# I2C_decagon_straight.net
KiCad netlist of a schematic drawn in EAGLE
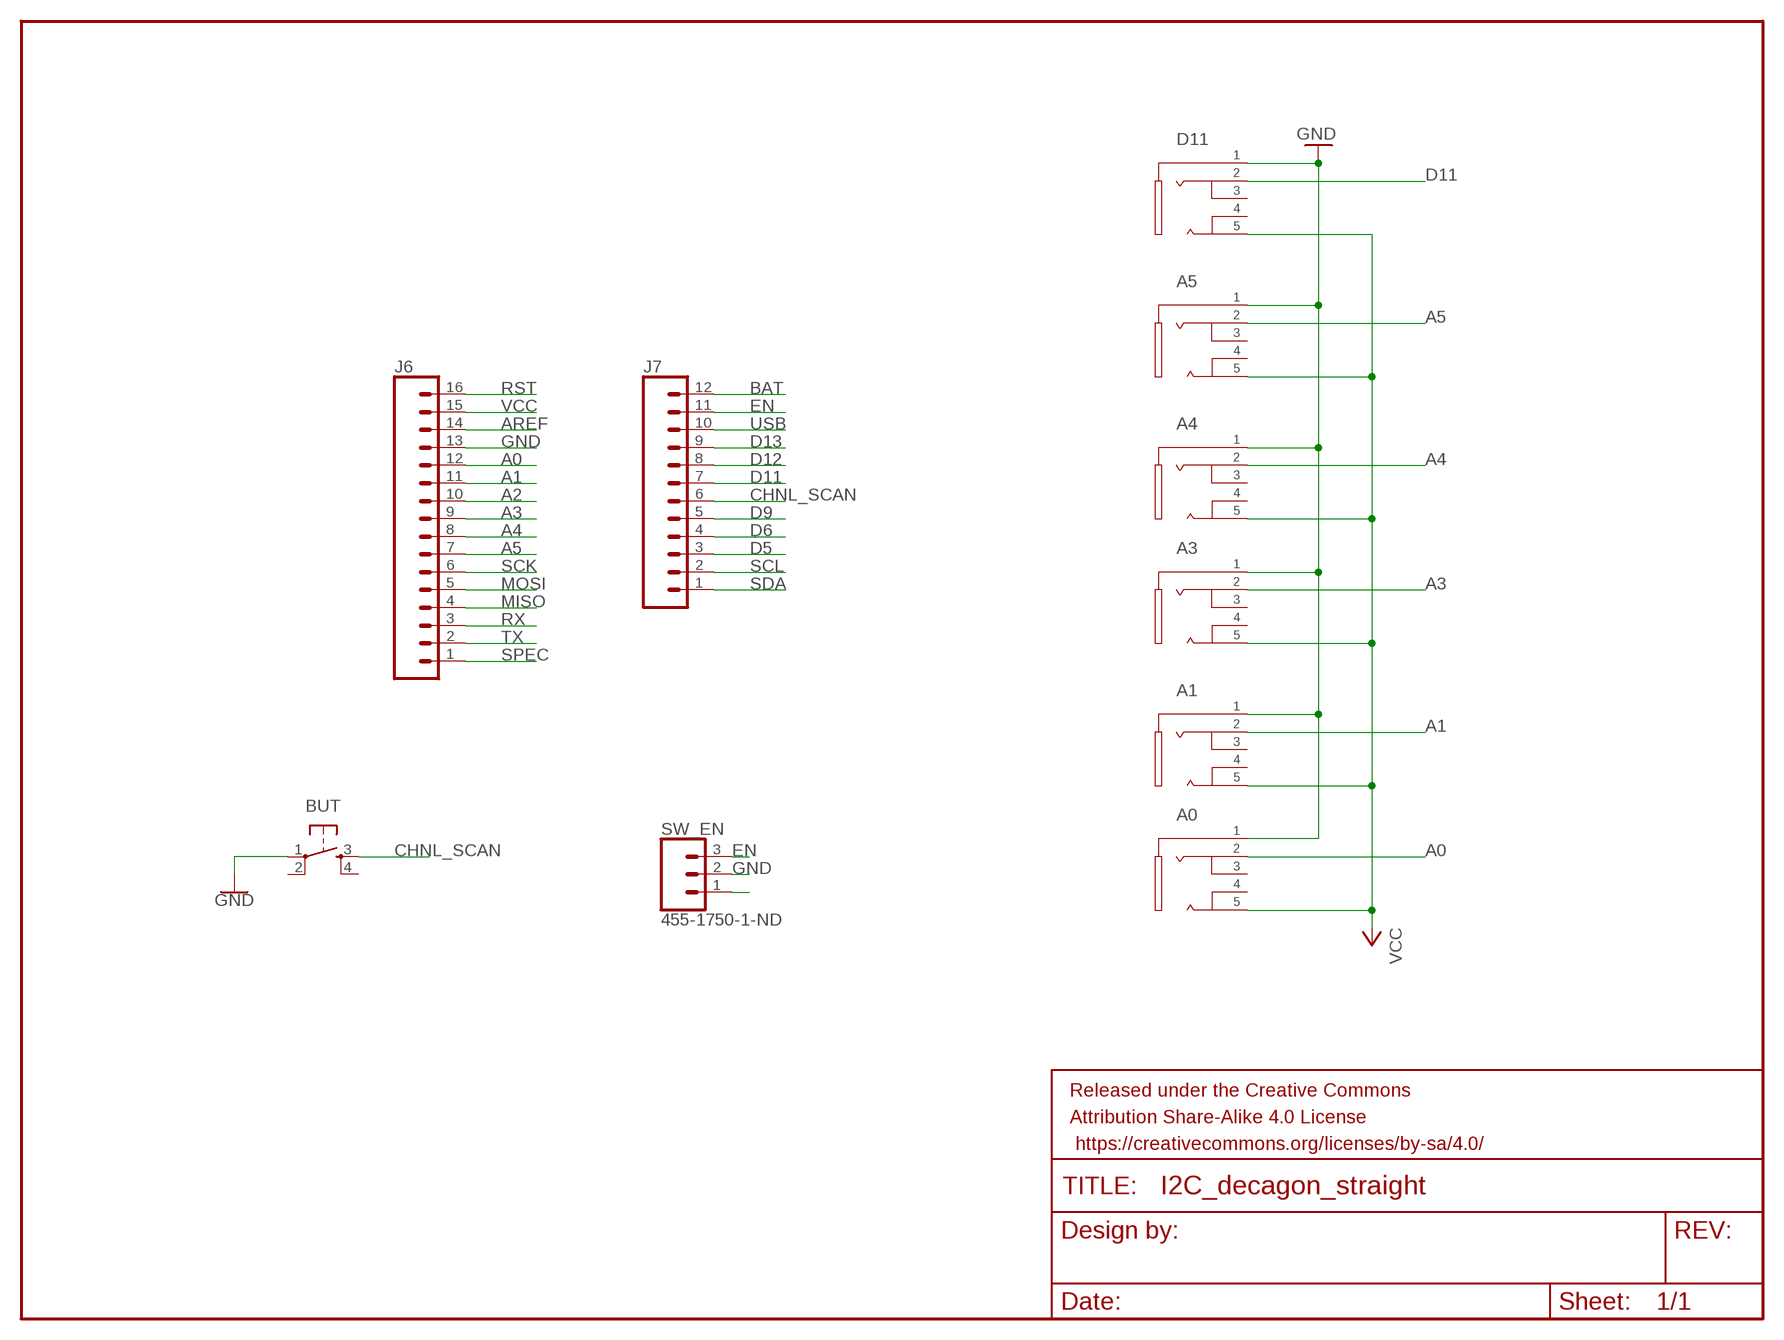
[diagram p0: schematic, sheet 1]

(export (version "E")
  (design (tool "Eeschema 10.0.6"))
  (components
    (comp (ref "A0")
      (value "JW-PJ-307-5H")
      (footprint "eagle-import:JW-PJ-307-5H")
      (libsource (lib "eagle-import") (part "JW-PJ-307-5H"))
    )
    (comp (ref "A1")
      (value "JW-PJ-307-5H")
      (footprint "eagle-import:JW-PJ-307-5H")
      (libsource (lib "eagle-import") (part "JW-PJ-307-5H"))
    )
    (comp (ref "A3")
      (value "JW-PJ-307-5H")
      (footprint "eagle-import:JW-PJ-307-5H")
      (libsource (lib "eagle-import") (part "JW-PJ-307-5H"))
    )
    (comp (ref "A4")
      (value "JW-PJ-307-5H")
      (footprint "eagle-import:JW-PJ-307-5H")
      (libsource (lib "eagle-import") (part "JW-PJ-307-5H"))
    )
    (comp (ref "A5")
      (value "JW-PJ-307-5H")
      (footprint "eagle-import:JW-PJ-307-5H")
      (libsource (lib "eagle-import") (part "JW-PJ-307-5H"))
    )
    (comp (ref "BUT")
      (value "TAC_SWITCHPTH")
      (footprint "eagle-import:TACTILE-PTH")
      (libsource (lib "eagle-import") (part "TAC_SWITCHPTH"))
    )
    (comp (ref "D11")
      (value "JW-PJ-307-5H")
      (footprint "eagle-import:JW-PJ-307-5H")
      (libsource (lib "eagle-import") (part "JW-PJ-307-5H"))
    )
    (comp (ref "FRAME1")
      (value "FRAME-LETTER")
      (footprint "eagle-import:CREATIVE_COMMONS")
      (libsource (lib "eagle-import") (part "FRAME-LETTER"))
    )
    (comp (ref "J6")
      (value "CONN_16")
      (footprint "eagle-import:1X16")
      (libsource (lib "eagle-import") (part "CONN_16"))
    )
    (comp (ref "J7")
      (value "CONN_12")
      (footprint "eagle-import:1X12")
      (libsource (lib "eagle-import") (part "CONN_12"))
    )
    (comp (ref "SW_EN")
      (value "455-1750-1-ND")
      (footprint "eagle-import:1X03")
      (libsource (lib "eagle-import") (part "CONN_03"))
    )
  )
  (nets
    (net (code "1") (name "/A0") (class "Default")
      (node (ref "A0") (pin "2") (pinfunction "2_2") (pintype "passive"))
      (node (ref "J6") (pin "12") (pinfunction "12_12") (pintype "passive"))
    )
    (net (code "2") (name "/A1") (class "Default")
      (node (ref "A1") (pin "2") (pinfunction "2_2") (pintype "passive"))
      (node (ref "J6") (pin "11") (pinfunction "11_11") (pintype "passive"))
    )
    (net (code "3") (name "/A2") (class "Default")
      (node (ref "J6") (pin "10") (pinfunction "10_10") (pintype "passive"))
    )
    (net (code "4") (name "/A3") (class "Default")
      (node (ref "A3") (pin "2") (pinfunction "2_2") (pintype "passive"))
      (node (ref "J6") (pin "9") (pinfunction "9_9") (pintype "passive"))
    )
    (net (code "5") (name "/A4") (class "Default")
      (node (ref "A4") (pin "2") (pinfunction "2_2") (pintype "passive"))
      (node (ref "J6") (pin "8") (pinfunction "8_8") (pintype "passive"))
    )
    (net (code "6") (name "/A5") (class "Default")
      (node (ref "A5") (pin "2") (pinfunction "2_2") (pintype "passive"))
      (node (ref "J6") (pin "7") (pinfunction "7_7") (pintype "passive"))
    )
    (net (code "7") (name "/AREF") (class "Default")
      (node (ref "J6") (pin "14") (pinfunction "14_14") (pintype "passive"))
    )
    (net (code "8") (name "/BAT") (class "Default")
      (node (ref "J7") (pin "12") (pinfunction "12_12") (pintype "passive"))
    )
    (net (code "9") (name "/CHNL_SCAN") (class "Default")
      (node (ref "BUT") (pin "3") (pinfunction "3_3") (pintype "passive"))
      (node (ref "J7") (pin "6") (pinfunction "6_6") (pintype "passive"))
    )
    (net (code "10") (name "/D5") (class "Default")
      (node (ref "J7") (pin "3") (pinfunction "3_3") (pintype "passive"))
    )
    (net (code "11") (name "/D6") (class "Default")
      (node (ref "J7") (pin "4") (pinfunction "4_4") (pintype "passive"))
    )
    (net (code "12") (name "/D9") (class "Default")
      (node (ref "J7") (pin "5") (pinfunction "5_5") (pintype "passive"))
    )
    (net (code "13") (name "/D11") (class "Default")
      (node (ref "D11") (pin "2") (pinfunction "2_2") (pintype "passive"))
      (node (ref "J7") (pin "7") (pinfunction "7_7") (pintype "passive"))
    )
    (net (code "14") (name "/D12") (class "Default")
      (node (ref "J7") (pin "8") (pinfunction "8_8") (pintype "passive"))
    )
    (net (code "15") (name "/D13") (class "Default")
      (node (ref "J7") (pin "9") (pinfunction "9_9") (pintype "passive"))
    )
    (net (code "16") (name "/EN") (class "Default")
      (node (ref "J7") (pin "11") (pinfunction "11_11") (pintype "passive"))
      (node (ref "SW_EN") (pin "3") (pinfunction "3_3") (pintype "passive"))
    )
    (net (code "17") (name "/MISO") (class "Default")
      (node (ref "J6") (pin "4") (pinfunction "4_4") (pintype "passive"))
    )
    (net (code "18") (name "/MOSI") (class "Default")
      (node (ref "J6") (pin "5") (pinfunction "5_5") (pintype "passive"))
    )
    (net (code "19") (name "/RST") (class "Default")
      (node (ref "J6") (pin "16") (pinfunction "16_16") (pintype "passive"))
    )
    (net (code "20") (name "/RX") (class "Default")
      (node (ref "J6") (pin "3") (pinfunction "3_3") (pintype "passive"))
    )
    (net (code "21") (name "/SCK") (class "Default")
      (node (ref "J6") (pin "6") (pinfunction "6_6") (pintype "passive"))
    )
    (net (code "22") (name "/SCL") (class "Default")
      (node (ref "J7") (pin "2") (pinfunction "2_2") (pintype "passive"))
    )
    (net (code "23") (name "/SDA") (class "Default")
      (node (ref "J7") (pin "1") (pinfunction "1_1") (pintype "passive"))
    )
    (net (code "24") (name "/SPEC") (class "Default")
      (node (ref "J6") (pin "1") (pinfunction "1_1") (pintype "passive"))
    )
    (net (code "25") (name "/TX") (class "Default")
      (node (ref "J6") (pin "2") (pinfunction "2_2") (pintype "passive"))
    )
    (net (code "26") (name "/USB") (class "Default")
      (node (ref "J7") (pin "10") (pinfunction "10_10") (pintype "passive"))
    )
    (net (code "27") (name "GND") (class "Default")
      (node (ref "A0") (pin "1") (pinfunction "1_1") (pintype "passive"))
      (node (ref "A1") (pin "1") (pinfunction "1_1") (pintype "passive"))
      (node (ref "A3") (pin "1") (pinfunction "1_1") (pintype "passive"))
      (node (ref "A4") (pin "1") (pinfunction "1_1") (pintype "passive"))
      (node (ref "A5") (pin "1") (pinfunction "1_1") (pintype "passive"))
      (node (ref "BUT") (pin "1") (pinfunction "1_1") (pintype "passive"))
      (node (ref "D11") (pin "1") (pinfunction "1_1") (pintype "passive"))
      (node (ref "J6") (pin "13") (pinfunction "13_13") (pintype "passive"))
      (node (ref "SW_EN") (pin "2") (pinfunction "2_2") (pintype "passive"))
    )
    (net (code "28") (name "VCC") (class "Default")
      (node (ref "A0") (pin "5") (pinfunction "5_5") (pintype "passive"))
      (node (ref "A1") (pin "5") (pinfunction "5_5") (pintype "passive"))
      (node (ref "A3") (pin "5") (pinfunction "5_5") (pintype "passive"))
      (node (ref "A4") (pin "5") (pinfunction "5_5") (pintype "passive"))
      (node (ref "A5") (pin "5") (pinfunction "5_5") (pintype "passive"))
      (node (ref "D11") (pin "5") (pinfunction "5_5") (pintype "passive"))
      (node (ref "J6") (pin "15") (pinfunction "15_15") (pintype "passive"))
    )
    (net (code "29") (name "unconnected-(A0-Pad3)") (class "Default")
      (node (ref "A0") (pin "3") (pinfunction "3_3") (pintype "passive"))
    )
    (net (code "30") (name "unconnected-(A0-Pad4)") (class "Default")
      (node (ref "A0") (pin "4") (pinfunction "4_4") (pintype "passive"))
    )
    (net (code "31") (name "unconnected-(A1-Pad3)") (class "Default")
      (node (ref "A1") (pin "3") (pinfunction "3_3") (pintype "passive"))
    )
    (net (code "32") (name "unconnected-(A1-Pad4)") (class "Default")
      (node (ref "A1") (pin "4") (pinfunction "4_4") (pintype "passive"))
    )
    (net (code "33") (name "unconnected-(A3-Pad3)") (class "Default")
      (node (ref "A3") (pin "3") (pinfunction "3_3") (pintype "passive"))
    )
    (net (code "34") (name "unconnected-(A3-Pad4)") (class "Default")
      (node (ref "A3") (pin "4") (pinfunction "4_4") (pintype "passive"))
    )
    (net (code "35") (name "unconnected-(A4-Pad3)") (class "Default")
      (node (ref "A4") (pin "3") (pinfunction "3_3") (pintype "passive"))
    )
    (net (code "36") (name "unconnected-(A4-Pad4)") (class "Default")
      (node (ref "A4") (pin "4") (pinfunction "4_4") (pintype "passive"))
    )
    (net (code "37") (name "unconnected-(A5-Pad3)") (class "Default")
      (node (ref "A5") (pin "3") (pinfunction "3_3") (pintype "passive"))
    )
    (net (code "38") (name "unconnected-(A5-Pad4)") (class "Default")
      (node (ref "A5") (pin "4") (pinfunction "4_4") (pintype "passive"))
    )
    (net (code "39") (name "unconnected-(BUT-Pad2)") (class "Default")
      (node (ref "BUT") (pin "2") (pinfunction "2_2") (pintype "passive"))
    )
    (net (code "40") (name "unconnected-(BUT-Pad4)") (class "Default")
      (node (ref "BUT") (pin "4") (pinfunction "4_4") (pintype "passive"))
    )
    (net (code "41") (name "unconnected-(D11-Pad3)") (class "Default")
      (node (ref "D11") (pin "3") (pinfunction "3_3") (pintype "passive"))
    )
    (net (code "42") (name "unconnected-(D11-Pad4)") (class "Default")
      (node (ref "D11") (pin "4") (pinfunction "4_4") (pintype "passive"))
    )
    (net (code "43") (name "unconnected-(SW_EN-Pad1)") (class "Default")
      (node (ref "SW_EN") (pin "1") (pinfunction "1_1") (pintype "passive"))
    )
  )
)
